# MB1046.net
KiCad netlist of a schematic drawn in Altium Designer
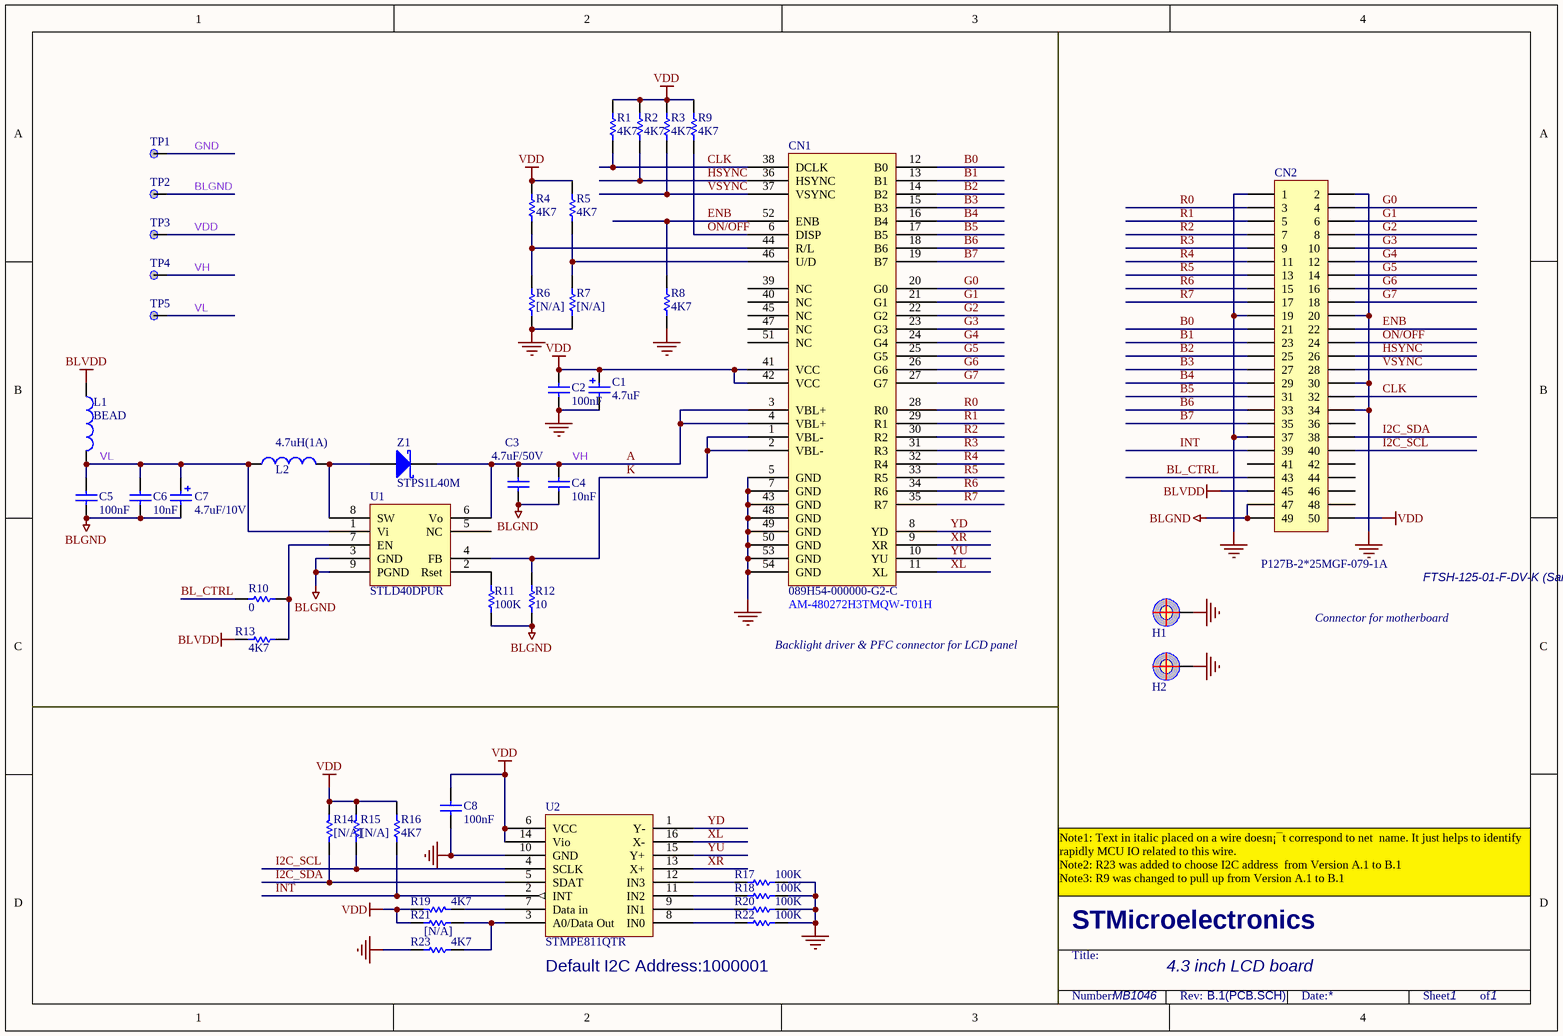
[diagram p0: MB1046.SchDoc]

(export (version "E")
  (design (tool "Eeschema 10.0.6"))
  (components
    (comp (ref "C1")
      (value "4.7uF")
      (footprint "TAN-A")
      (description "Polarized Capacitor (Radial)")
      (fields (field (name "PUBLISHER") "Altium Limited"))
      (libsource (lib "Miscellaneous Devices") (part "Cap Pol1"))
    )
    (comp (ref "C2")
      (value "100nF")
      (footprint "0603C")
      (description "Capacitor")
      (fields (field (name "PUBLISHER") "Altium Limited"))
      (libsource (lib "Miscellaneous Devices") (part "CAP"))
    )
    (comp (ref "C3")
      (value "4.7uF/50V")
      (footprint "1206C")
      (description "Capacitor")
      (fields (field (name "PUBLISHER") "Altium Limited"))
      (libsource (lib "Miscellaneous Devices") (part "CAP"))
    )
    (comp (ref "C4")
      (value "10nF")
      (footprint "0603C")
      (description "Capacitor")
      (fields (field (name "PUBLISHER") "Altium Limited"))
      (libsource (lib "*") (part "CAP"))
    )
    (comp (ref "C5")
      (value "100nF")
      (footprint "0603C")
      (description "Capacitor")
      (fields (field (name "PUBLISHER") "Altium Limited"))
      (libsource (lib "Miscellaneous Devices") (part "CAP"))
    )
    (comp (ref "C6")
      (value "10nF")
      (footprint "0603C")
      (description "Capacitor")
      (fields (field (name "PUBLISHER") "Altium Limited"))
      (libsource (lib "Miscellaneous Devices") (part "CAP"))
    )
    (comp (ref "C7")
      (value "4.7uF/10V")
      (footprint "1206C")
      (description "Polarized Capacitor (Radial)")
      (fields (field (name "PUBLISHER") "Altium Limited"))
      (libsource (lib "Miscellaneous Devices") (part "Cap Pol1"))
    )
    (comp (ref "C8")
      (value "100nF")
      (footprint "0603C")
      (description "Capacitor")
      (fields (field (name "PUBLISHER") "Altium Limited"))
      (libsource (lib "Miscellaneous Devices") (part "CAP"))
    )
    (comp (ref "CN1")
      (value "089H54-000000-G2-C")
      (footprint "FPC54_0R5_089H54_LY-FPC")
      (libsource (lib "MB1046") (part "089H54-000000-G2-C"))
    )
    (comp (ref "CN2")
      (value "P127B-2*25MGF-079-1A")
      (footprint "FTSH-125-01-F-DV")
      (description "Header, 26-Pin, Dual row")
      (fields (field (name "PUBLISHER") "Altium Limited"))
      (libsource (lib "mb1045") (part "Header 25X2"))
    )
    (comp (ref "H1")
      (value "POSITION HOLE")
      (footprint "HOLE_C9D4R5")
      (libsource (lib "mb1045") (part "POSITION HOLE"))
    )
    (comp (ref "H2")
      (value "POSITION HOLE")
      (footprint "HOLE_C9D4R5")
      (libsource (lib "mb1045") (part "POSITION HOLE"))
    )
    (comp (ref "L1")
      (value "BEAD")
      (footprint "0603L")
      (description "Inductor")
      (fields (field (name "PUBLISHER") "Altium Limited"))
      (libsource (lib "Miscellaneous Devices") (part "Inductor"))
    )
    (comp (ref "L2")
      (value "4.7uH(1A)")
      (footprint "1210L")
      (description "Inductor")
      (fields (field (name "PUBLISHER") "Altium Limited"))
      (libsource (lib "Miscellaneous Devices") (part "Inductor"))
    )
    (comp (ref "R1")
      (value "4K7")
      (footprint "0603R")
      (description "Resistor")
      (fields (field (name "PUBLISHER") "Altium Limited"))
      (libsource (lib "*") (part "Res1"))
    )
    (comp (ref "R2")
      (value "4K7")
      (footprint "0603R")
      (description "Resistor")
      (fields (field (name "PUBLISHER") "Altium Limited"))
      (libsource (lib "*") (part "Res1"))
    )
    (comp (ref "R3")
      (value "4K7")
      (footprint "0603R")
      (description "Resistor")
      (fields (field (name "PUBLISHER") "Altium Limited"))
      (libsource (lib "*") (part "Res1"))
    )
    (comp (ref "R4")
      (value "4K7")
      (footprint "0603R")
      (description "Resistor")
      (fields (field (name "PUBLISHER") "Altium Limited"))
      (libsource (lib "*") (part "Res1"))
    )
    (comp (ref "R5")
      (value "4K7")
      (footprint "0603R")
      (description "Resistor")
      (fields (field (name "PUBLISHER") "Altium Limited"))
      (libsource (lib "*") (part "Res1"))
    )
    (comp (ref "R6")
      (value "[N/A]")
      (footprint "0603R")
      (description "Resistor")
      (fields (field (name "PUBLISHER") "Altium Limited"))
      (libsource (lib "*") (part "Res1"))
    )
    (comp (ref "R7")
      (value "[N/A]")
      (footprint "0603R")
      (description "Resistor")
      (fields (field (name "PUBLISHER") "Altium Limited"))
      (libsource (lib "*") (part "Res1"))
    )
    (comp (ref "R8")
      (value "4K7")
      (footprint "0603R")
      (description "Resistor")
      (fields (field (name "PUBLISHER") "Altium Limited"))
      (libsource (lib "*") (part "Res1"))
    )
    (comp (ref "R9")
      (value "4K7")
      (footprint "0603R")
      (description "Resistor")
      (fields (field (name "PUBLISHER") "Altium Limited"))
      (libsource (lib "*") (part "Res1"))
    )
    (comp (ref "R10")
      (value "0")
      (footprint "0603R")
      (description "Resistor")
      (fields (field (name "PUBLISHER") "Altium Limited"))
      (libsource (lib "Miscellaneous Devices") (part "Res1"))
    )
    (comp (ref "R11")
      (value "100K")
      (footprint "0603R")
      (description "Resistor")
      (fields (field (name "PUBLISHER") "Altium Limited"))
      (libsource (lib "Miscellaneous Devices") (part "Res1"))
    )
    (comp (ref "R12")
      (value "10")
      (footprint "0603R")
      (description "Resistor")
      (fields (field (name "PUBLISHER") "Altium Limited"))
      (libsource (lib "Miscellaneous Devices") (part "Res1"))
    )
    (comp (ref "R13")
      (value "4K7")
      (footprint "0603R")
      (description "Resistor")
      (fields (field (name "PUBLISHER") "Altium Limited"))
      (libsource (lib "Miscellaneous Devices") (part "Res1"))
    )
    (comp (ref "R14")
      (value "[N/A]")
      (footprint "0603R")
      (description "Resistor")
      (fields (field (name "PUBLISHER") "Altium Limited"))
      (libsource (lib "*") (part "Res1"))
    )
    (comp (ref "R15")
      (value "[N/A]")
      (footprint "0603R")
      (description "Resistor")
      (fields (field (name "PUBLISHER") "Altium Limited"))
      (libsource (lib "*") (part "Res1"))
    )
    (comp (ref "R16")
      (value "4K7")
      (footprint "0603R")
      (description "Resistor")
      (fields (field (name "PUBLISHER") "Altium Limited"))
      (libsource (lib "*") (part "Res1"))
    )
    (comp (ref "R17")
      (value "100K")
      (footprint "0603R")
      (description "Resistor")
      (fields (field (name "PUBLISHER") "Altium Limited"))
      (libsource (lib "MB915_1") (part "res1"))
    )
    (comp (ref "R18")
      (value "100K")
      (footprint "0603R")
      (description "Resistor")
      (fields (field (name "PUBLISHER") "Altium Limited"))
      (libsource (lib "MB915_1") (part "res1"))
    )
    (comp (ref "R19")
      (value "4K7")
      (footprint "0603R")
      (description "Resistor")
      (fields (field (name "PUBLISHER") "Altium Limited"))
      (libsource (lib "") (part "Res1_1"))
    )
    (comp (ref "R20")
      (value "100K")
      (footprint "0603R")
      (description "Resistor")
      (fields (field (name "PUBLISHER") "Altium Limited"))
      (libsource (lib "MB915_1") (part "res1"))
    )
    (comp (ref "R21")
      (value "[N/A]")
      (footprint "0603R")
      (description "Resistor")
      (fields (field (name "PUBLISHER") "Altium Limited"))
      (libsource (lib "Miscellaneous Devices") (part "Res1"))
    )
    (comp (ref "R22")
      (value "100K")
      (footprint "0603R")
      (description "Resistor")
      (fields (field (name "PUBLISHER") "Altium Limited"))
      (libsource (lib "MB915_1") (part "res1"))
    )
    (comp (ref "R23")
      (value "4K7")
      (footprint "0603R")
      (description "Resistor")
      (fields (field (name "PUBLISHER") "Altium Limited"))
      (libsource (lib "*") (part "Res1"))
    )
    (comp (ref "TP1") (value "~") (footprint "TP") (libsource (lib "*") (part "TP")))
    (comp (ref "TP2") (value "~") (footprint "TP") (libsource (lib "*") (part "TP")))
    (comp (ref "TP3") (value "~") (footprint "TP") (libsource (lib "*") (part "TP")))
    (comp (ref "TP4") (value "~") (footprint "TP") (libsource (lib "*") (part "TP")))
    (comp (ref "TP5") (value "~") (footprint "TP") (libsource (lib "*") (part "TP")))
    (comp (ref "U1")
      (value "STLD40DPUR")
      (footprint "SON8_0R65_3X3")
      (libsource (lib "3.2LCD_daughterboard") (part "STLD40DPMR"))
    )
    (comp (ref "U2")
      (value "STMPE811QTR")
      (footprint "QFN16_0R5_3X3")
      (libsource (lib "MB784") (part "STMPE811"))
    )
    (comp (ref "Z1")
      (value "STPS1L40M")
      (footprint "DO-216AA")
      (description "Schottky Diode")
      (fields (field (name "PUBLISHER") "Altium Limited"))
      (libsource (lib "Miscellaneous Devices") (part "D Schottky"))
    )
  )
  (nets
    (net (code "1") (name "/A") (class "Default")
      (node (ref "C3") (pin "1") (pinfunction "1_1") (pintype "passive"))
      (node (ref "C4") (pin "2") (pinfunction "2_2") (pintype "passive"))
      (node (ref "CN1") (pin "3") (pinfunction "VBL+_3") (pintype "passive"))
      (node (ref "CN1") (pin "4") (pinfunction "VBL+_4") (pintype "passive"))
      (node (ref "TP4") (pin "1") (pinfunction "1_1") (pintype "passive"))
      (node (ref "U1") (pin "6") (pinfunction "Vo_6") (pintype "passive"))
      (node (ref "Z1") (pin "2") (pinfunction "K_2") (pintype "passive"))
    )
    (net (code "2") (name "/B0") (class "Default")
      (node (ref "CN1") (pin "12") (pinfunction "B0_12") (pintype "passive"))
      (node (ref "CN2") (pin "21") (pinfunction "21_21") (pintype "passive"))
    )
    (net (code "3") (name "/B1") (class "Default")
      (node (ref "CN1") (pin "13") (pinfunction "B1_13") (pintype "passive"))
      (node (ref "CN2") (pin "23") (pinfunction "23_23") (pintype "passive"))
    )
    (net (code "4") (name "/B2") (class "Default")
      (node (ref "CN1") (pin "14") (pinfunction "B2_14") (pintype "passive"))
      (node (ref "CN2") (pin "25") (pinfunction "25_25") (pintype "passive"))
    )
    (net (code "5") (name "/B3") (class "Default")
      (node (ref "CN1") (pin "15") (pinfunction "B3_15") (pintype "passive"))
      (node (ref "CN2") (pin "27") (pinfunction "27_27") (pintype "passive"))
    )
    (net (code "6") (name "/B4") (class "Default")
      (node (ref "CN1") (pin "16") (pinfunction "B4_16") (pintype "passive"))
      (node (ref "CN2") (pin "29") (pinfunction "29_29") (pintype "passive"))
    )
    (net (code "7") (name "/B5") (class "Default")
      (node (ref "CN1") (pin "17") (pinfunction "B5_17") (pintype "passive"))
      (node (ref "CN2") (pin "31") (pinfunction "31_31") (pintype "passive"))
    )
    (net (code "8") (name "/B6") (class "Default")
      (node (ref "CN1") (pin "18") (pinfunction "B6_18") (pintype "passive"))
      (node (ref "CN2") (pin "33") (pinfunction "33_33") (pintype "passive"))
    )
    (net (code "9") (name "/B7") (class "Default")
      (node (ref "CN1") (pin "19") (pinfunction "B7_19") (pintype "passive"))
      (node (ref "CN2") (pin "35") (pinfunction "35_35") (pintype "passive"))
    )
    (net (code "10") (name "/BL_CTRL") (class "Default")
      (node (ref "CN2") (pin "43") (pinfunction "43_43") (pintype "passive"))
      (node (ref "R10") (pin "2") (pinfunction "2_2") (pintype "passive"))
    )
    (net (code "11") (name "/CLK") (class "Default")
      (node (ref "CN1") (pin "38") (pinfunction "DCLK_38") (pintype "passive"))
      (node (ref "CN2") (pin "32") (pinfunction "32_32") (pintype "passive"))
      (node (ref "R1") (pin "2") (pinfunction "2_2") (pintype "passive"))
    )
    (net (code "12") (name "/ENB") (class "Default")
      (node (ref "CN1") (pin "52") (pinfunction "ENB_52") (pintype "passive"))
      (node (ref "CN2") (pin "22") (pinfunction "22_22") (pintype "passive"))
      (node (ref "R8") (pin "1") (pinfunction "1_1") (pintype "passive"))
    )
    (net (code "13") (name "/G0") (class "Default")
      (node (ref "CN1") (pin "20") (pinfunction "G0_20") (pintype "passive"))
      (node (ref "CN2") (pin "4") (pinfunction "4_4") (pintype "passive"))
    )
    (net (code "14") (name "/G1") (class "Default")
      (node (ref "CN1") (pin "21") (pinfunction "G1_21") (pintype "passive"))
      (node (ref "CN2") (pin "6") (pinfunction "6_6") (pintype "passive"))
    )
    (net (code "15") (name "/G2") (class "Default")
      (node (ref "CN1") (pin "22") (pinfunction "G2_22") (pintype "passive"))
      (node (ref "CN2") (pin "8") (pinfunction "8_8") (pintype "passive"))
    )
    (net (code "16") (name "/G3") (class "Default")
      (node (ref "CN1") (pin "23") (pinfunction "G3_23") (pintype "passive"))
      (node (ref "CN2") (pin "10") (pinfunction "10_10") (pintype "passive"))
    )
    (net (code "17") (name "/G4") (class "Default")
      (node (ref "CN1") (pin "24") (pinfunction "G4_24") (pintype "passive"))
      (node (ref "CN2") (pin "12") (pinfunction "12_12") (pintype "passive"))
    )
    (net (code "18") (name "/G5") (class "Default")
      (node (ref "CN1") (pin "25") (pinfunction "G5_25") (pintype "passive"))
      (node (ref "CN2") (pin "14") (pinfunction "14_14") (pintype "passive"))
    )
    (net (code "19") (name "/G6") (class "Default")
      (node (ref "CN1") (pin "26") (pinfunction "G6_26") (pintype "passive"))
      (node (ref "CN2") (pin "16") (pinfunction "16_16") (pintype "passive"))
    )
    (net (code "20") (name "/G7") (class "Default")
      (node (ref "CN1") (pin "27") (pinfunction "G7_27") (pintype "passive"))
      (node (ref "CN2") (pin "18") (pinfunction "18_18") (pintype "passive"))
    )
    (net (code "21") (name "/HSYNC") (class "Default")
      (node (ref "CN1") (pin "36") (pinfunction "HSYNC_36") (pintype "passive"))
      (node (ref "CN2") (pin "26") (pinfunction "26_26") (pintype "passive"))
      (node (ref "R2") (pin "2") (pinfunction "2_2") (pintype "passive"))
    )
    (net (code "22") (name "/I2C_SCL") (class "Default")
      (node (ref "CN2") (pin "40") (pinfunction "40_40") (pintype "passive"))
      (node (ref "R15") (pin "1") (pinfunction "1_1") (pintype "passive"))
      (node (ref "U2") (pin "4") (pinfunction "SCLK_4") (pintype "passive"))
    )
    (net (code "23") (name "/I2C_SDA") (class "Default")
      (node (ref "CN2") (pin "38") (pinfunction "38_38") (pintype "passive"))
      (node (ref "R14") (pin "1") (pinfunction "1_1") (pintype "passive"))
      (node (ref "U2") (pin "5") (pinfunction "SDAT_5") (pintype "passive"))
    )
    (net (code "24") (name "/INT") (class "Default")
      (node (ref "CN2") (pin "39") (pinfunction "39_39") (pintype "passive"))
      (node (ref "R16") (pin "2") (pinfunction "2_2") (pintype "passive"))
      (node (ref "U2") (pin "2") (pinfunction "INT_2") (pintype "output"))
    )
    (net (code "25") (name "/K") (class "Default")
      (node (ref "CN1") (pin "1") (pinfunction "VBL-_1") (pintype "passive"))
      (node (ref "CN1") (pin "2") (pinfunction "VBL-_2") (pintype "passive"))
      (node (ref "R12") (pin "2") (pinfunction "2_2") (pintype "passive"))
      (node (ref "U1") (pin "4") (pinfunction "FB_4") (pintype "passive"))
    )
    (net (code "26") (name "/ON{slash}OFF") (class "Default")
      (node (ref "CN1") (pin "6") (pinfunction "DISP_6") (pintype "passive"))
      (node (ref "CN2") (pin "24") (pinfunction "24_24") (pintype "passive"))
      (node (ref "R9") (pin "2") (pinfunction "2_2") (pintype "passive"))
    )
    (net (code "27") (name "/R0") (class "Default")
      (node (ref "CN1") (pin "28") (pinfunction "R0_28") (pintype "passive"))
      (node (ref "CN2") (pin "3") (pinfunction "3_3") (pintype "passive"))
    )
    (net (code "28") (name "/R1") (class "Default")
      (node (ref "CN1") (pin "29") (pinfunction "R1_29") (pintype "passive"))
      (node (ref "CN2") (pin "5") (pinfunction "5_5") (pintype "passive"))
    )
    (net (code "29") (name "/R2") (class "Default")
      (node (ref "CN1") (pin "30") (pinfunction "R2_30") (pintype "passive"))
      (node (ref "CN2") (pin "7") (pinfunction "7_7") (pintype "passive"))
    )
    (net (code "30") (name "/R3") (class "Default")
      (node (ref "CN1") (pin "31") (pinfunction "R3_31") (pintype "passive"))
      (node (ref "CN2") (pin "9") (pinfunction "9_9") (pintype "passive"))
    )
    (net (code "31") (name "/R4") (class "Default")
      (node (ref "CN1") (pin "32") (pinfunction "R4_32") (pintype "passive"))
      (node (ref "CN2") (pin "11") (pinfunction "11_11") (pintype "passive"))
    )
    (net (code "32") (name "/R5") (class "Default")
      (node (ref "CN1") (pin "33") (pinfunction "R5_33") (pintype "passive"))
      (node (ref "CN2") (pin "13") (pinfunction "13_13") (pintype "passive"))
    )
    (net (code "33") (name "/R6") (class "Default")
      (node (ref "CN1") (pin "34") (pinfunction "R6_34") (pintype "passive"))
      (node (ref "CN2") (pin "15") (pinfunction "15_15") (pintype "passive"))
    )
    (net (code "34") (name "/R7") (class "Default")
      (node (ref "CN1") (pin "35") (pinfunction "R7_35") (pintype "passive"))
      (node (ref "CN2") (pin "17") (pinfunction "17_17") (pintype "passive"))
    )
    (net (code "35") (name "/VL") (class "Default")
      (node (ref "C5") (pin "2") (pinfunction "2_2") (pintype "passive"))
      (node (ref "C6") (pin "2") (pinfunction "2_2") (pintype "passive"))
      (node (ref "C7") (pin "1") (pinfunction "1_1") (pintype "passive"))
      (node (ref "L1") (pin "2") (pinfunction "2_2") (pintype "passive"))
      (node (ref "L2") (pin "1") (pinfunction "1_1") (pintype "passive"))
      (node (ref "TP5") (pin "1") (pinfunction "1_1") (pintype "passive"))
      (node (ref "U1") (pin "1") (pinfunction "Vi_1") (pintype "passive"))
    )
    (net (code "36") (name "/VSYNC") (class "Default")
      (node (ref "CN1") (pin "37") (pinfunction "VSYNC_37") (pintype "passive"))
      (node (ref "CN2") (pin "28") (pinfunction "28_28") (pintype "passive"))
      (node (ref "R3") (pin "2") (pinfunction "2_2") (pintype "passive"))
    )
    (net (code "37") (name "/XL") (class "Default")
      (node (ref "CN1") (pin "11") (pinfunction "XL_11") (pintype "passive"))
      (node (ref "U2") (pin "16") (pinfunction "X-_16") (pintype "passive"))
    )
    (net (code "38") (name "/XR") (class "Default")
      (node (ref "CN1") (pin "9") (pinfunction "XR_9") (pintype "passive"))
      (node (ref "U2") (pin "13") (pinfunction "X+_13") (pintype "passive"))
    )
    (net (code "39") (name "/YD") (class "Default")
      (node (ref "CN1") (pin "8") (pinfunction "YD_8") (pintype "passive"))
      (node (ref "U2") (pin "1") (pinfunction "Y-_1") (pintype "passive"))
    )
    (net (code "40") (name "/YU") (class "Default")
      (node (ref "CN1") (pin "10") (pinfunction "YU_10") (pintype "passive"))
      (node (ref "U2") (pin "15") (pinfunction "Y+_15") (pintype "passive"))
    )
    (net (code "41") (name "BLGND") (class "Default")
      (node (ref "C3") (pin "2") (pinfunction "2_2") (pintype "passive"))
      (node (ref "C4") (pin "1") (pinfunction "1_1") (pintype "passive"))
      (node (ref "C5") (pin "1") (pinfunction "1_1") (pintype "passive"))
      (node (ref "C6") (pin "1") (pinfunction "1_1") (pintype "passive"))
      (node (ref "C7") (pin "2") (pinfunction "2_2") (pintype "passive"))
      (node (ref "CN2") (pin "47") (pinfunction "47_47") (pintype "passive"))
      (node (ref "CN2") (pin "49") (pinfunction "49_49") (pintype "passive"))
      (node (ref "R11") (pin "2") (pinfunction "2_2") (pintype "passive"))
      (node (ref "R12") (pin "1") (pinfunction "1_1") (pintype "passive"))
      (node (ref "TP2") (pin "1") (pinfunction "1_1") (pintype "passive"))
      (node (ref "U1") (pin "3") (pinfunction "GND_3") (pintype "passive"))
      (node (ref "U1") (pin "9") (pinfunction "PGND_9") (pintype "passive"))
    )
    (net (code "42") (name "BLVDD") (class "Default")
      (node (ref "CN2") (pin "45") (pinfunction "45_45") (pintype "passive"))
      (node (ref "L1") (pin "1") (pinfunction "1_1") (pintype "passive"))
      (node (ref "R13") (pin "2") (pinfunction "2_2") (pintype "passive"))
    )
    (net (code "43") (name "GND") (class "Default")
      (node (ref "C1") (pin "2") (pinfunction "2_2") (pintype "passive"))
      (node (ref "C2") (pin "1") (pinfunction "1_1") (pintype "passive"))
      (node (ref "C8") (pin "2") (pinfunction "2_2") (pintype "passive"))
      (node (ref "CN1") (pin "43") (pinfunction "GND_43") (pintype "passive"))
      (node (ref "CN1") (pin "48") (pinfunction "GND_48") (pintype "passive"))
      (node (ref "CN1") (pin "49") (pinfunction "GND_49") (pintype "passive"))
      (node (ref "CN1") (pin "5") (pinfunction "GND_5") (pintype "passive"))
      (node (ref "CN1") (pin "50") (pinfunction "GND_50") (pintype "passive"))
      (node (ref "CN1") (pin "53") (pinfunction "GND_53") (pintype "passive"))
      (node (ref "CN1") (pin "54") (pinfunction "GND_54") (pintype "passive"))
      (node (ref "CN1") (pin "7") (pinfunction "GND_7") (pintype "passive"))
      (node (ref "CN2") (pin "1") (pinfunction "1_1") (pintype "passive"))
      (node (ref "CN2") (pin "19") (pinfunction "19_19") (pintype "passive"))
      (node (ref "CN2") (pin "2") (pinfunction "2_2") (pintype "passive"))
      (node (ref "CN2") (pin "20") (pinfunction "20_20") (pintype "passive"))
      (node (ref "CN2") (pin "30") (pinfunction "30_30") (pintype "passive"))
      (node (ref "CN2") (pin "34") (pinfunction "34_34") (pintype "passive"))
      (node (ref "CN2") (pin "37") (pinfunction "37_37") (pintype "passive"))
      (node (ref "H1") (pin "1") (pinfunction "1_1") (pintype "passive"))
      (node (ref "H2") (pin "1") (pinfunction "1_1") (pintype "passive"))
      (node (ref "R17") (pin "1") (pinfunction "1_1") (pintype "passive"))
      (node (ref "R18") (pin "1") (pinfunction "1_1") (pintype "passive"))
      (node (ref "R20") (pin "1") (pinfunction "1_1") (pintype "passive"))
      (node (ref "R22") (pin "1") (pinfunction "1_1") (pintype "passive"))
      (node (ref "R23") (pin "1") (pinfunction "1_1") (pintype "passive"))
      (node (ref "R6") (pin "2") (pinfunction "2_2") (pintype "passive"))
      (node (ref "R7") (pin "2") (pinfunction "2_2") (pintype "passive"))
      (node (ref "R8") (pin "2") (pinfunction "2_2") (pintype "passive"))
      (node (ref "TP1") (pin "1") (pinfunction "1_1") (pintype "passive"))
      (node (ref "U2") (pin "10") (pinfunction "GND_10") (pintype "passive"))
    )
    (net (code "44") (name "Net-(CN1-R{slash}L)") (class "Default")
      (node (ref "CN1") (pin "44") (pinfunction "R/L_44") (pintype "passive"))
      (node (ref "R4") (pin "2") (pinfunction "2_2") (pintype "passive"))
      (node (ref "R6") (pin "1") (pinfunction "1_1") (pintype "passive"))
    )
    (net (code "45") (name "Net-(CN1-U{slash}D)") (class "Default")
      (node (ref "CN1") (pin "46") (pinfunction "U/D_46") (pintype "passive"))
      (node (ref "R5") (pin "2") (pinfunction "2_2") (pintype "passive"))
      (node (ref "R7") (pin "1") (pinfunction "1_1") (pintype "passive"))
    )
    (net (code "46") (name "Net-(U1-EN)") (class "Default")
      (node (ref "R10") (pin "1") (pinfunction "1_1") (pintype "passive"))
      (node (ref "R13") (pin "1") (pinfunction "1_1") (pintype "passive"))
      (node (ref "U1") (pin "7") (pinfunction "EN_7") (pintype "passive"))
    )
    (net (code "47") (name "Net-(U1-Rset)") (class "Default")
      (node (ref "R11") (pin "1") (pinfunction "1_1") (pintype "passive"))
      (node (ref "U1") (pin "2") (pinfunction "Rset_2") (pintype "passive"))
    )
    (net (code "48") (name "Net-(U1-SW)") (class "Default")
      (node (ref "L2") (pin "2") (pinfunction "2_2") (pintype "passive"))
      (node (ref "U1") (pin "8") (pinfunction "SW_8") (pintype "passive"))
      (node (ref "Z1") (pin "1") (pinfunction "A_1") (pintype "passive"))
    )
    (net (code "49") (name "Net-(U2-A0{slash}Data_Out)") (class "Default")
      (node (ref "R21") (pin "1") (pinfunction "1_1") (pintype "passive"))
      (node (ref "R23") (pin "2") (pinfunction "2_2") (pintype "passive"))
      (node (ref "U2") (pin "3") (pinfunction "A0/Data_Out_3") (pintype "passive"))
    )
    (net (code "50") (name "Net-(U2-Data_in)") (class "Default")
      (node (ref "R19") (pin "1") (pinfunction "1_1") (pintype "passive"))
      (node (ref "U2") (pin "7") (pinfunction "Data_in_7") (pintype "passive"))
    )
    (net (code "51") (name "Net-(U2-IN0)") (class "Default")
      (node (ref "R22") (pin "2") (pinfunction "2_2") (pintype "passive"))
      (node (ref "U2") (pin "8") (pinfunction "IN0_8") (pintype "passive"))
    )
    (net (code "52") (name "Net-(U2-IN1)") (class "Default")
      (node (ref "R20") (pin "2") (pinfunction "2_2") (pintype "passive"))
      (node (ref "U2") (pin "9") (pinfunction "IN1_9") (pintype "passive"))
    )
    (net (code "53") (name "Net-(U2-IN2)") (class "Default")
      (node (ref "R18") (pin "2") (pinfunction "2_2") (pintype "passive"))
      (node (ref "U2") (pin "11") (pinfunction "IN2_11") (pintype "passive"))
    )
    (net (code "54") (name "Net-(U2-IN3)") (class "Default")
      (node (ref "R17") (pin "2") (pinfunction "2_2") (pintype "passive"))
      (node (ref "U2") (pin "12") (pinfunction "IN3_12") (pintype "passive"))
    )
    (net (code "55") (name "VDD") (class "Default")
      (node (ref "C1") (pin "1") (pinfunction "1_1") (pintype "passive"))
      (node (ref "C2") (pin "2") (pinfunction "2_2") (pintype "passive"))
      (node (ref "C8") (pin "1") (pinfunction "1_1") (pintype "passive"))
      (node (ref "CN1") (pin "41") (pinfunction "VCC_41") (pintype "passive"))
      (node (ref "CN1") (pin "42") (pinfunction "VCC_42") (pintype "passive"))
      (node (ref "CN2") (pin "50") (pinfunction "50_50") (pintype "passive"))
      (node (ref "R1") (pin "1") (pinfunction "1_1") (pintype "passive"))
      (node (ref "R14") (pin "2") (pinfunction "2_2") (pintype "passive"))
      (node (ref "R15") (pin "2") (pinfunction "2_2") (pintype "passive"))
      (node (ref "R16") (pin "1") (pinfunction "1_1") (pintype "passive"))
      (node (ref "R19") (pin "2") (pinfunction "2_2") (pintype "passive"))
      (node (ref "R2") (pin "1") (pinfunction "1_1") (pintype "passive"))
      (node (ref "R21") (pin "2") (pinfunction "2_2") (pintype "passive"))
      (node (ref "R3") (pin "1") (pinfunction "1_1") (pintype "passive"))
      (node (ref "R4") (pin "1") (pinfunction "1_1") (pintype "passive"))
      (node (ref "R5") (pin "1") (pinfunction "1_1") (pintype "passive"))
      (node (ref "R9") (pin "1") (pinfunction "1_1") (pintype "passive"))
      (node (ref "TP3") (pin "1") (pinfunction "1_1") (pintype "passive"))
      (node (ref "U2") (pin "14") (pinfunction "Vio_14") (pintype "passive"))
      (node (ref "U2") (pin "6") (pinfunction "VCC_6") (pintype "passive"))
    )
    (net (code "56") (name "unconnected-(CN1-NC-Pad39)") (class "Default")
      (node (ref "CN1") (pin "39") (pinfunction "NC_39") (pintype "passive"))
    )
    (net (code "57") (name "unconnected-(CN1-NC-Pad40)") (class "Default")
      (node (ref "CN1") (pin "40") (pinfunction "NC_40") (pintype "passive"))
    )
    (net (code "58") (name "unconnected-(CN1-NC-Pad45)") (class "Default")
      (node (ref "CN1") (pin "45") (pinfunction "NC_45") (pintype "passive"))
    )
    (net (code "59") (name "unconnected-(CN1-NC-Pad47)") (class "Default")
      (node (ref "CN1") (pin "47") (pinfunction "NC_47") (pintype "passive"))
    )
    (net (code "60") (name "unconnected-(CN1-NC-Pad51)") (class "Default")
      (node (ref "CN1") (pin "51") (pinfunction "NC_51") (pintype "passive"))
    )
    (net (code "61") (name "unconnected-(CN2-Pad36)") (class "Default")
      (node (ref "CN2") (pin "36") (pinfunction "36_36") (pintype "passive"))
    )
    (net (code "62") (name "unconnected-(CN2-Pad41)") (class "Default")
      (node (ref "CN2") (pin "41") (pinfunction "41_41") (pintype "passive"))
    )
    (net (code "63") (name "unconnected-(CN2-Pad42)") (class "Default")
      (node (ref "CN2") (pin "42") (pinfunction "42_42") (pintype "passive"))
    )
    (net (code "64") (name "unconnected-(CN2-Pad44)") (class "Default")
      (node (ref "CN2") (pin "44") (pinfunction "44_44") (pintype "passive"))
    )
    (net (code "65") (name "unconnected-(CN2-Pad46)") (class "Default")
      (node (ref "CN2") (pin "46") (pinfunction "46_46") (pintype "passive"))
    )
    (net (code "66") (name "unconnected-(CN2-Pad48)") (class "Default")
      (node (ref "CN2") (pin "48") (pinfunction "48_48") (pintype "passive"))
    )
    (net (code "67") (name "unconnected-(U1-NC-Pad5)") (class "Default")
      (node (ref "U1") (pin "5") (pinfunction "NC_5") (pintype "passive"))
    )
  )
)
